# esc_servo.net
KiCad netlist of a schematic drawn in Altium Designer
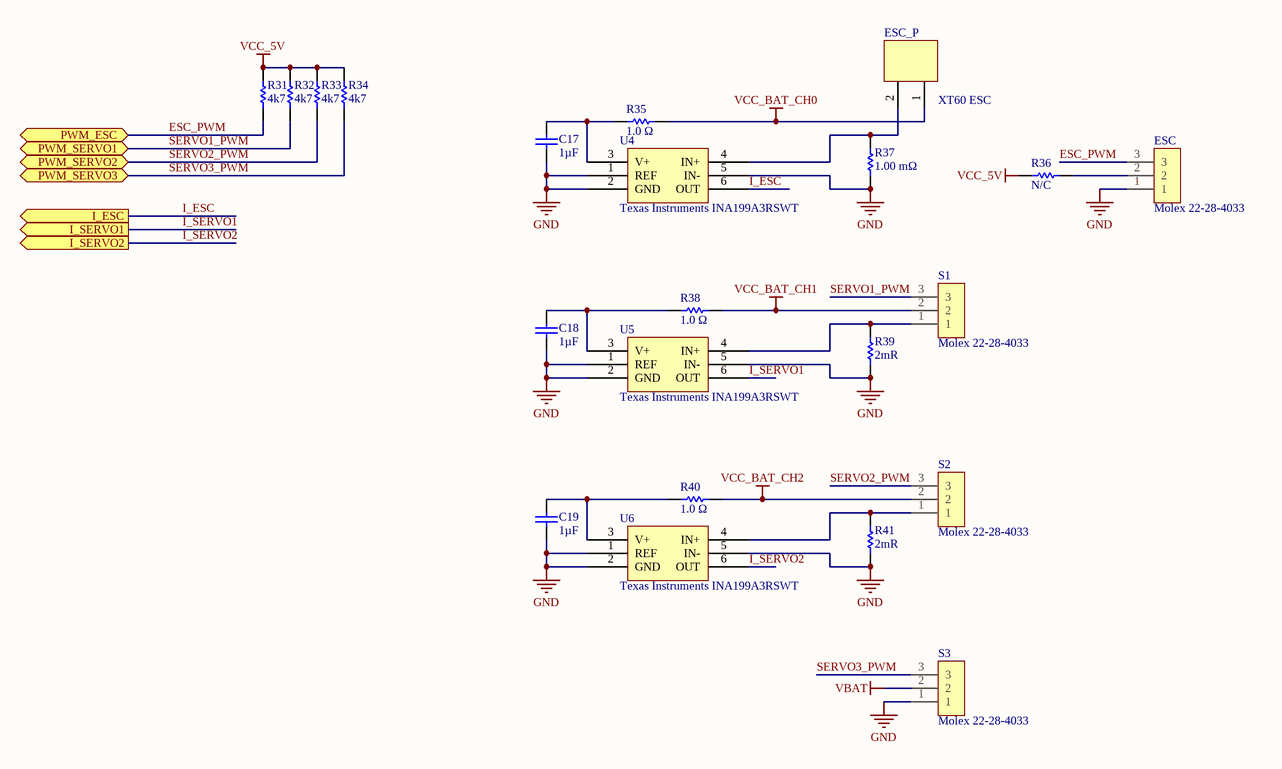
[diagram p0: esc_servo.SchDoc]

(export (version "E")
  (design (tool "Eeschema 10.0.6"))
  (components
    (comp (ref "C17")
      (value "1µF")
      (footprint "CAPC1608X90X35LL15T15")
      (description "0603 1 uF 16 V ±10 % Tolerance X5R SMT Multilayer Ceramic Capacitor")
      (libsource (lib "CommunityVault") (part "CAP-NP-2"))
    )
    (comp (ref "C18")
      (value "1µF")
      (footprint "CAPC1608X90X35LL15T15")
      (description "0603 1 uF 16 V ±10 % Tolerance X5R SMT Multilayer Ceramic Capacitor")
      (libsource (lib "CommunityVault") (part "CAP-NP-2"))
    )
    (comp (ref "C19")
      (value "1µF")
      (footprint "CAPC1608X90X35LL15T15")
      (description "0603 1 uF 16 V ±10 % Tolerance X5R SMT Multilayer Ceramic Capacitor")
      (libsource (lib "CommunityVault") (part "CAP-NP-2"))
    )
    (comp (ref "ESC")
      (value "Molex 22-28-4033")
      (footprint "PCB-8kup8qw5vsmkearo8v0b-1")
      (description "SERVAL TRIJUMPER")
      (fields (field (name "MANUFACTURER PART NUMBER") "22-28-4033"))
      (libsource (lib "CommunityVault") (part "SYM-b995709ba24d6652-10"))
    )
    (comp (ref "ESC_P")
      (value "XT60 ESC")
      (footprint "PCB-8tmbcd94dx0l5ponnqur-1")
      (description "XT60 Connector Male")
      (libsource (lib "CommunityVault") (part "CMP-d8151592827e07d2-9"))
    )
    (comp (ref "R31")
      (value "4k7")
      (footprint "RESC1608X55X30NL15T15")
      (description "Res Thick Film 0603 4.7K Ohm 1% 1/10W ±100ppm/°C Molded SMD Paper T/R")
      (libsource (lib "CommunityVault") (part "RES-2"))
    )
    (comp (ref "R32")
      (value "4k7")
      (footprint "RESC1608X55X30NL15T15")
      (description "Res Thick Film 0603 4.7K Ohm 1% 1/10W ±100ppm/°C Molded SMD Paper T/R")
      (libsource (lib "CommunityVault") (part "RES-2"))
    )
    (comp (ref "R33")
      (value "4k7")
      (footprint "RESC1608X55X30NL15T15")
      (description "Res Thick Film 0603 4.7K Ohm 1% 1/10W ±100ppm/°C Molded SMD Paper T/R")
      (libsource (lib "CommunityVault") (part "RES-2"))
    )
    (comp (ref "R34")
      (value "4k7")
      (footprint "RESC1608X55X30NL15T15")
      (description "Res Thick Film 0603 4.7K Ohm 1% 1/10W ±100ppm/°C Molded SMD Paper T/R")
      (libsource (lib "CommunityVault") (part "RES-2"))
    )
    (comp (ref "R35")
      (value "1.0 Ω")
      (footprint "RESC1609X50X30LL10T20")
      (description "RES SMD 1 OHM 5% 1/10W 0603")
      (fields (field (name "MANUFACTURER PART NUMBER") "CRCW06031R00JNEA"))
      (libsource (lib "CommunityVault") (part "CMP-1856057-2"))
    )
    (comp (ref "R36")
      (value "N/C")
      (footprint "RESC1608X55X25LL10T15")
      (description "Thick Film Resistors - SMD ZERO OHM JUMPER")
      (libsource (lib "CommunityVault") (part "CMP-3661350-4"))
    )
    (comp (ref "R37")
      (value "1.00 mΩ")
      (footprint "PCB-wws5gc0zzodyoofoa1sn-1")
      (description "Res Thick Film 2512 0.001 Ohm 1% 3W ±50ppm/C Pad SMD Automotive T/R")
      (fields (field (name "MANUFACTURER PART NUMBER") "CRE2512-FZ-R001E-3"))
      (libsource (lib "CommunityVault") (part "CMP-5c9b974035f1835c-1"))
    )
    (comp (ref "R38")
      (value "1.0 Ω")
      (footprint "RESC1609X50X30LL10T20")
      (description "RES SMD 1 OHM 5% 1/10W 0603")
      (fields (field (name "MANUFACTURER PART NUMBER") "CRCW06031R00JNEA"))
      (libsource (lib "CommunityVault") (part "CMP-1856057-2"))
    )
    (comp (ref "R39")
      (value "2mR")
      (footprint "RESC3216X89X51ML25T25")
      (description "Res Metal Strip 1206 0.02 Ohm 1% 0.25W(1/4W) ±75ppm/C Molded SMD Automotive Embossed Plastic T/R")
      (fields (field (name "MANUFACTURER PART NUMBER") "WSL1206R0200FEA"))
      (libsource (lib "CommunityVault") (part "CMP-1863047-2"))
    )
    (comp (ref "R40")
      (value "1.0 Ω")
      (footprint "RESC1609X50X30LL10T20")
      (description "RES SMD 1 OHM 5% 1/10W 0603")
      (fields (field (name "MANUFACTURER PART NUMBER") "CRCW06031R00JNEA"))
      (libsource (lib "CommunityVault") (part "CMP-1856057-2"))
    )
    (comp (ref "R41")
      (value "2mR")
      (footprint "RESC3216X89X51ML25T25")
      (description "Res Metal Strip 1206 0.02 Ohm 1% 0.25W(1/4W) ±75ppm/C Molded SMD Automotive Embossed Plastic T/R")
      (fields (field (name "MANUFACTURER PART NUMBER") "WSL1206R0200FEA"))
      (libsource (lib "CommunityVault") (part "CMP-1863047-2"))
    )
    (comp (ref "S1")
      (value "Molex 22-28-4033")
      (footprint "PCB-8kup8qw5vsmkearo8v0b-1")
      (description "SERVAL TRIJUMPER")
      (fields (field (name "MANUFACTURER PART NUMBER") "22-28-4033"))
      (libsource (lib "CommunityVault") (part "CMP-b995709ba24d6652-18"))
    )
    (comp (ref "S2")
      (value "Molex 22-28-4033")
      (footprint "PCB-8kup8qw5vsmkearo8v0b-1")
      (description "SERVAL TRIJUMPER")
      (fields (field (name "MANUFACTURER PART NUMBER") "22-28-4033"))
      (libsource (lib "CommunityVault") (part "SYM-b995709ba24d6652-10"))
    )
    (comp (ref "S3")
      (value "Molex 22-28-4033")
      (footprint "PCB-8kup8qw5vsmkearo8v0b-1")
      (description "SERVAL TRIJUMPER")
      (fields (field (name "MANUFACTURER PART NUMBER") "22-28-4033"))
      (libsource (lib "CommunityVault") (part "SYM-b995709ba24d6652-10"))
    )
    (comp (ref "U4")
      (value "Texas Instruments INA199A3RSWT")
      (footprint "PCB-dzg43p1s5wcf61j10amz-1")
      (libsource (lib "CommunityVault") (part "SYM-0f05c77d0cddd0c2-7"))
    )
    (comp (ref "U5")
      (value "Texas Instruments INA199A3RSWT")
      (footprint "PCB-dzg43p1s5wcf61j10amz-1")
      (libsource (lib "CommunityVault") (part "SYM-0f05c77d0cddd0c2-7"))
    )
    (comp (ref "U6")
      (value "Texas Instruments INA199A3RSWT")
      (footprint "PCB-dzg43p1s5wcf61j10amz-1")
      (libsource (lib "CommunityVault") (part "SYM-0f05c77d0cddd0c2-7"))
    )
  )
  (nets
    (net (code "1") (name "/ESC_PWM") (class "Default")
      (node (ref "ESC") (pin "3") (pinfunction "3_3") (pintype "passive"))
      (node (ref "R31") (pin "1") (pinfunction "1_1") (pintype "passive"))
    )
    (net (code "2") (name "/I_ESC") (class "Default")
      (node (ref "U4") (pin "6") (pinfunction "OUT_6") (pintype "passive"))
    )
    (net (code "3") (name "/I_SERVO1") (class "Default")
      (node (ref "U5") (pin "6") (pinfunction "OUT_6") (pintype "passive"))
    )
    (net (code "4") (name "/I_SERVO2") (class "Default")
      (node (ref "U6") (pin "6") (pinfunction "OUT_6") (pintype "passive"))
    )
    (net (code "5") (name "/SERVO1_PWM") (class "Default")
      (node (ref "R32") (pin "1") (pinfunction "1_1") (pintype "passive"))
      (node (ref "S1") (pin "3") (pinfunction "3_3") (pintype "passive"))
    )
    (net (code "6") (name "/SERVO2_PWM") (class "Default")
      (node (ref "R33") (pin "1") (pinfunction "1_1") (pintype "passive"))
      (node (ref "S2") (pin "3") (pinfunction "3_3") (pintype "passive"))
    )
    (net (code "7") (name "/SERVO3_PWM") (class "Default")
      (node (ref "R34") (pin "1") (pinfunction "1_1") (pintype "passive"))
      (node (ref "S3") (pin "3") (pinfunction "3_3") (pintype "passive"))
    )
    (net (code "8") (name "GND") (class "Default")
      (node (ref "C17") (pin "2") (pinfunction "2_2") (pintype "passive"))
      (node (ref "C18") (pin "2") (pinfunction "2_2") (pintype "passive"))
      (node (ref "C19") (pin "2") (pinfunction "2_2") (pintype "passive"))
      (node (ref "ESC") (pin "1") (pinfunction "1_1") (pintype "passive"))
      (node (ref "R37") (pin "1") (pinfunction "1_1") (pintype "passive"))
      (node (ref "R39") (pin "1") (pinfunction "1_1") (pintype "passive"))
      (node (ref "R41") (pin "1") (pinfunction "1_1") (pintype "passive"))
      (node (ref "S3") (pin "1") (pinfunction "1_1") (pintype "passive"))
      (node (ref "U4") (pin "1") (pinfunction "REF_1") (pintype "passive"))
      (node (ref "U4") (pin "2") (pinfunction "GND_2") (pintype "passive"))
      (node (ref "U4") (pin "5") (pinfunction "IN-_5") (pintype "passive"))
      (node (ref "U5") (pin "1") (pinfunction "REF_1") (pintype "passive"))
      (node (ref "U5") (pin "2") (pinfunction "GND_2") (pintype "passive"))
      (node (ref "U5") (pin "5") (pinfunction "IN-_5") (pintype "passive"))
      (node (ref "U6") (pin "1") (pinfunction "REF_1") (pintype "passive"))
      (node (ref "U6") (pin "2") (pinfunction "GND_2") (pintype "passive"))
      (node (ref "U6") (pin "5") (pinfunction "IN-_5") (pintype "passive"))
    )
    (net (code "9") (name "Net-(ESC-Pad2)") (class "Default")
      (node (ref "ESC") (pin "2") (pinfunction "2_2") (pintype "passive"))
      (node (ref "R36") (pin "1") (pinfunction "1_1") (pintype "passive"))
    )
    (net (code "10") (name "Net-(U4-IN+)") (class "Default")
      (node (ref "ESC_P") (pin "2") (pinfunction "2_2") (pintype "passive"))
      (node (ref "R37") (pin "2") (pinfunction "2_2") (pintype "passive"))
      (node (ref "U4") (pin "4") (pinfunction "IN+_4") (pintype "passive"))
    )
    (net (code "11") (name "Net-(U4-V+)") (class "Default")
      (node (ref "C17") (pin "1") (pinfunction "1_1") (pintype "passive"))
      (node (ref "R35") (pin "1") (pinfunction "1_1") (pintype "passive"))
      (node (ref "U4") (pin "3") (pinfunction "V+_3") (pintype "passive"))
    )
    (net (code "12") (name "Net-(U5-IN+)") (class "Default")
      (node (ref "R39") (pin "2") (pinfunction "2_2") (pintype "passive"))
      (node (ref "S1") (pin "1") (pinfunction "1_1") (pintype "passive"))
      (node (ref "U5") (pin "4") (pinfunction "IN+_4") (pintype "passive"))
    )
    (net (code "13") (name "Net-(U5-V+)") (class "Default")
      (node (ref "C18") (pin "1") (pinfunction "1_1") (pintype "passive"))
      (node (ref "R38") (pin "1") (pinfunction "1_1") (pintype "passive"))
      (node (ref "U5") (pin "3") (pinfunction "V+_3") (pintype "passive"))
    )
    (net (code "14") (name "Net-(U6-IN+)") (class "Default")
      (node (ref "R41") (pin "2") (pinfunction "2_2") (pintype "passive"))
      (node (ref "S2") (pin "1") (pinfunction "1_1") (pintype "passive"))
      (node (ref "U6") (pin "4") (pinfunction "IN+_4") (pintype "passive"))
    )
    (net (code "15") (name "Net-(U6-V+)") (class "Default")
      (node (ref "C19") (pin "1") (pinfunction "1_1") (pintype "passive"))
      (node (ref "R40") (pin "1") (pinfunction "1_1") (pintype "passive"))
      (node (ref "U6") (pin "3") (pinfunction "V+_3") (pintype "passive"))
    )
    (net (code "16") (name "VBAT") (class "Default")
      (node (ref "S3") (pin "2") (pinfunction "2_2") (pintype "passive"))
    )
    (net (code "17") (name "VCC_5V") (class "Default")
      (node (ref "R31") (pin "2") (pinfunction "2_2") (pintype "passive"))
      (node (ref "R32") (pin "2") (pinfunction "2_2") (pintype "passive"))
      (node (ref "R33") (pin "2") (pinfunction "2_2") (pintype "passive"))
      (node (ref "R34") (pin "2") (pinfunction "2_2") (pintype "passive"))
      (node (ref "R36") (pin "2") (pinfunction "2_2") (pintype "passive"))
    )
    (net (code "18") (name "VCC_BAT_CH0") (class "Default")
      (node (ref "ESC_P") (pin "1") (pinfunction "1_1") (pintype "passive"))
      (node (ref "R35") (pin "2") (pinfunction "2_2") (pintype "passive"))
    )
    (net (code "19") (name "VCC_BAT_CH1") (class "Default")
      (node (ref "R38") (pin "2") (pinfunction "2_2") (pintype "passive"))
      (node (ref "S1") (pin "2") (pinfunction "2_2") (pintype "passive"))
    )
    (net (code "20") (name "VCC_BAT_CH2") (class "Default")
      (node (ref "R40") (pin "2") (pinfunction "2_2") (pintype "passive"))
      (node (ref "S2") (pin "2") (pinfunction "2_2") (pintype "passive"))
    )
  )
)
